# lm709_discrete.net
KiCad netlist of a schematic drawn in EAGLE
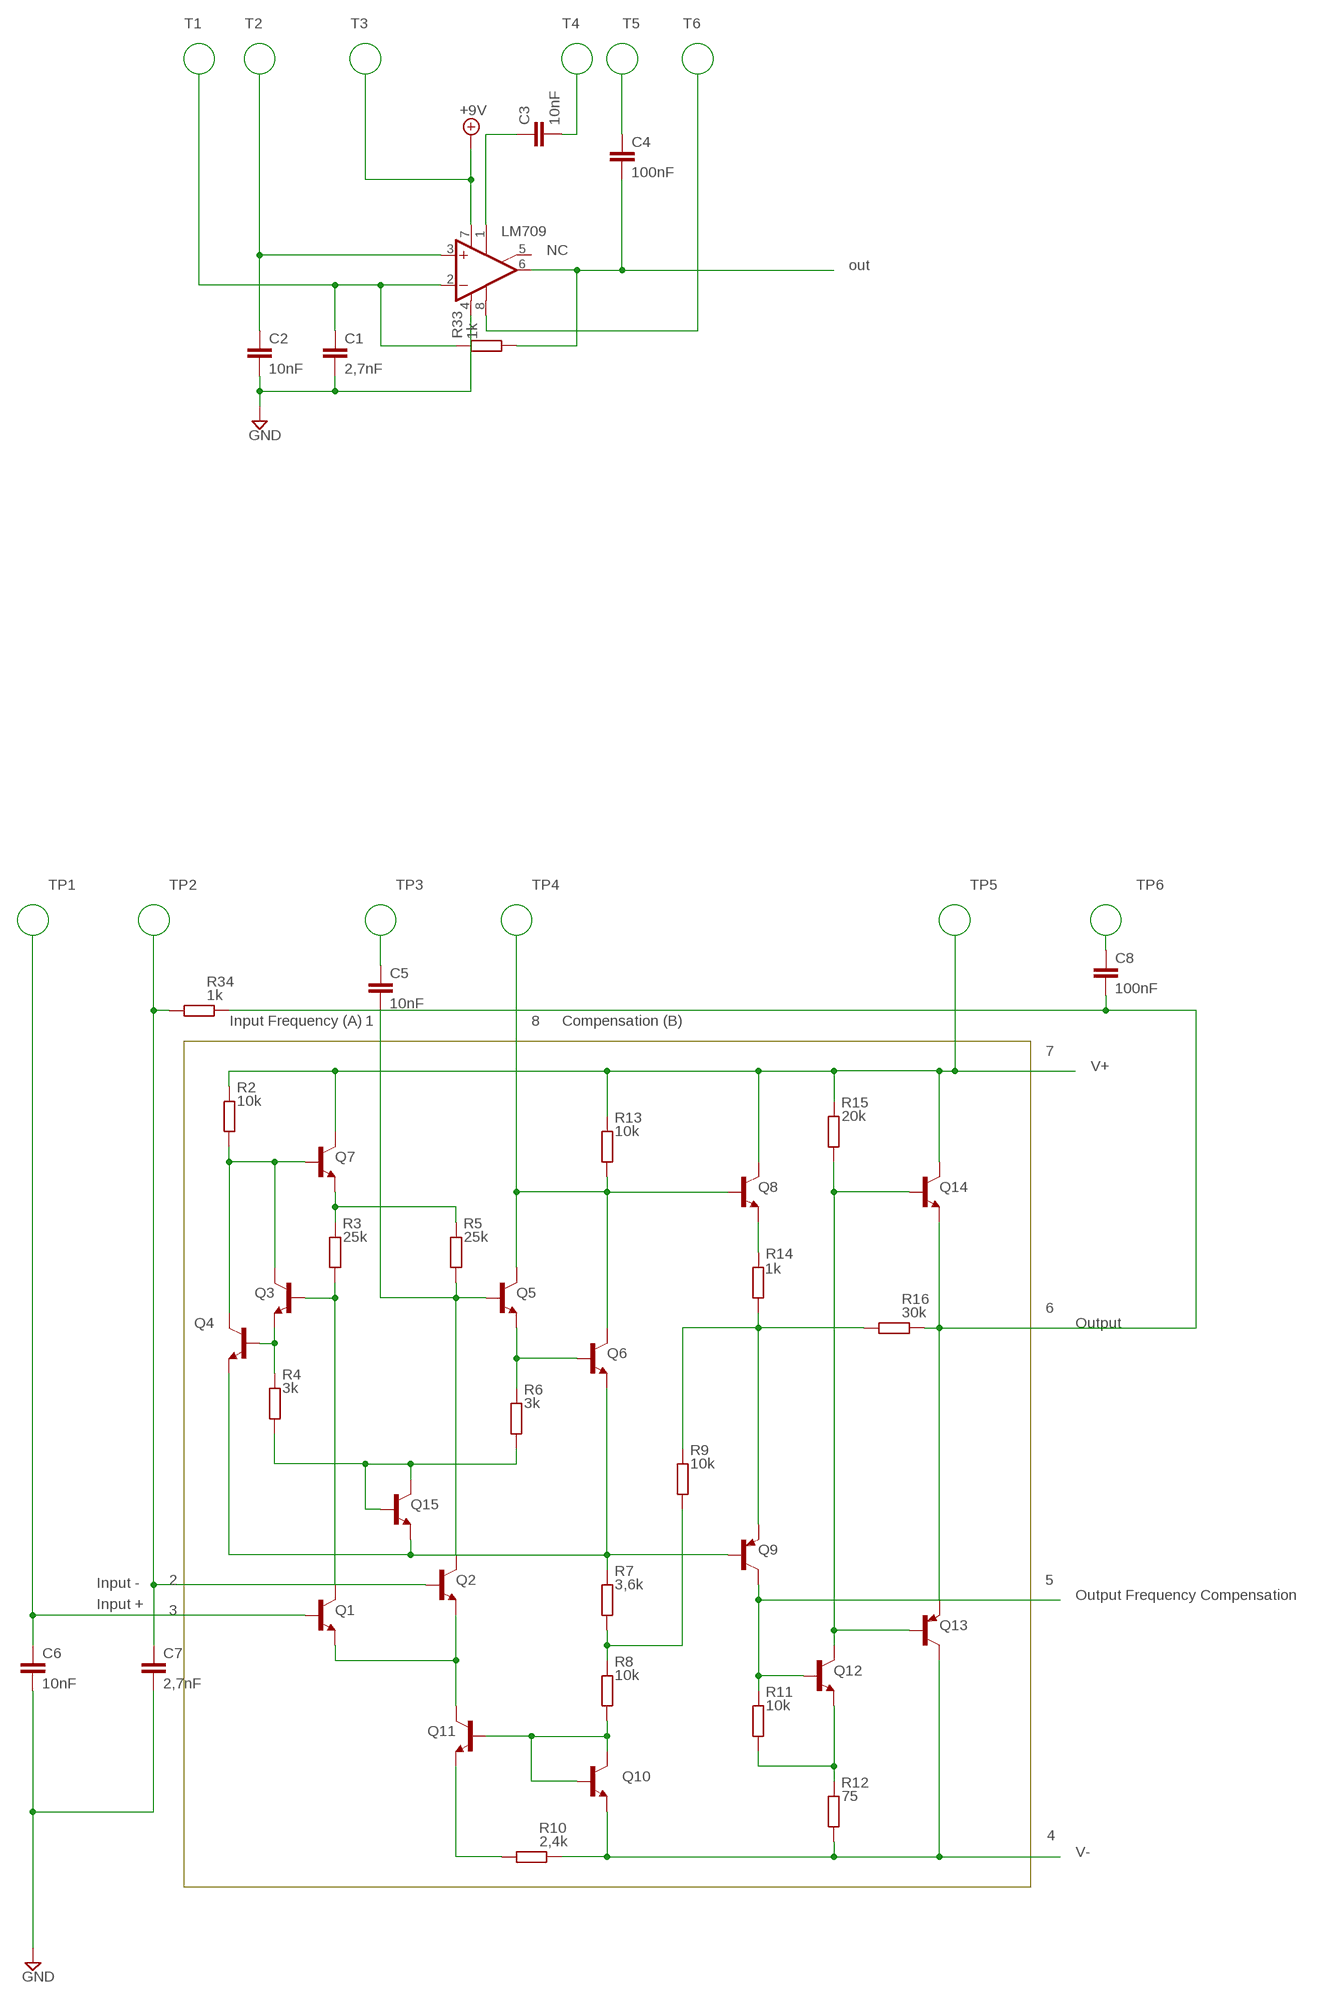
[diagram p0: schematic, sheet 1]
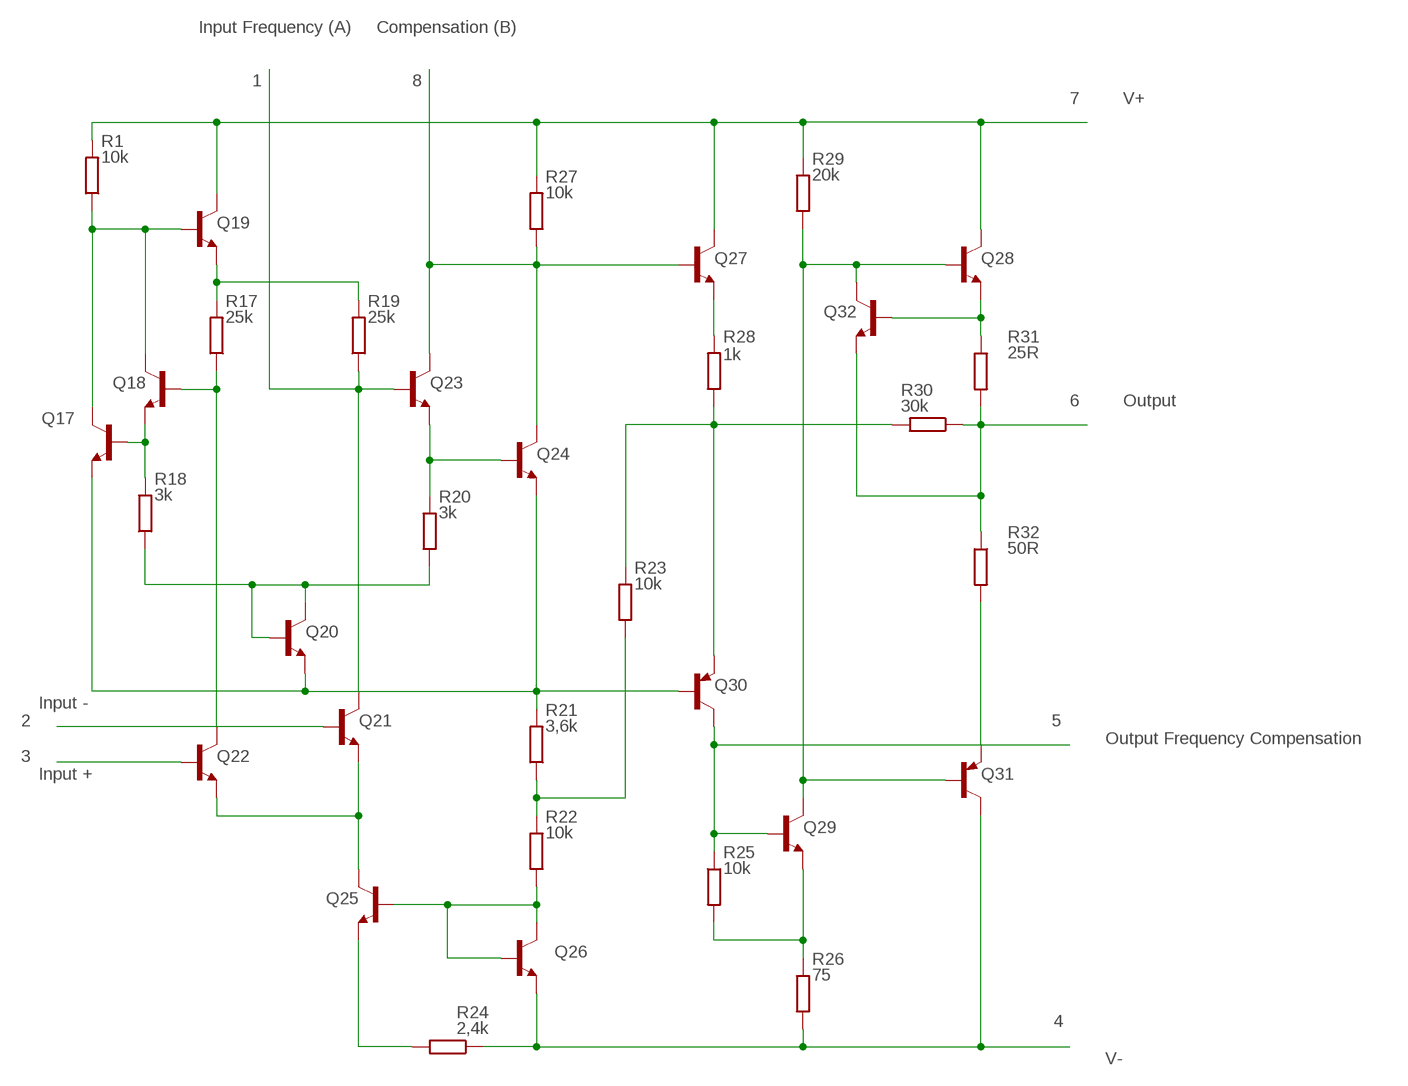
[diagram p1: schematic, sheet 2]

(export (version "E")
  (design (tool "Eeschema 10.0.6"))
  (components
    (comp (ref "C1")
      (value "2,7nF")
      (footprint "eagle-import:C025-024X044")
      (libsource (lib "eagle-import") (part "C-EU025-024X044"))
    )
    (comp (ref "C2")
      (value "10nF")
      (footprint "eagle-import:C025-024X044")
      (libsource (lib "eagle-import") (part "C-EU025-024X044"))
    )
    (comp (ref "C3")
      (value "10nF")
      (footprint "eagle-import:C025-024X044")
      (libsource (lib "eagle-import") (part "C-EU025-024X044"))
    )
    (comp (ref "C4")
      (value "100nF")
      (footprint "eagle-import:C025-024X044")
      (libsource (lib "eagle-import") (part "C-EU025-024X044"))
    )
    (comp (ref "C5")
      (value "10nF")
      (footprint "eagle-import:C025-024X044")
      (libsource (lib "eagle-import") (part "C-EU025-024X044"))
    )
    (comp (ref "C6")
      (value "10nF")
      (footprint "eagle-import:C025-024X044")
      (libsource (lib "eagle-import") (part "C-EU025-024X044"))
    )
    (comp (ref "C7")
      (value "2,7nF")
      (footprint "eagle-import:C025-024X044")
      (libsource (lib "eagle-import") (part "C-EU025-024X044"))
    )
    (comp (ref "C8")
      (value "100nF")
      (footprint "eagle-import:C025-024X044")
      (libsource (lib "eagle-import") (part "C-EU025-024X044"))
    )
    (comp (ref "LM709")
      (value "LM741P")
      (footprint "eagle-import:DIL08")
      (libsource (lib "eagle-import") (part "741PLM"))
    )
    (comp (ref "Q1")
      (value "2N3904")
      (footprint "eagle-import:TO92")
      (libsource (lib "eagle-import") (part "2N3904"))
    )
    (comp (ref "Q2")
      (value "2N3904")
      (footprint "eagle-import:TO92")
      (libsource (lib "eagle-import") (part "2N3904"))
    )
    (comp (ref "Q3")
      (value "2N3904")
      (footprint "eagle-import:TO92")
      (libsource (lib "eagle-import") (part "2N3904"))
    )
    (comp (ref "Q4")
      (value "2N3904")
      (footprint "eagle-import:TO92")
      (libsource (lib "eagle-import") (part "2N3904"))
    )
    (comp (ref "Q5")
      (value "2N3904")
      (footprint "eagle-import:TO92")
      (libsource (lib "eagle-import") (part "2N3904"))
    )
    (comp (ref "Q6")
      (value "2N3904")
      (footprint "eagle-import:TO92")
      (libsource (lib "eagle-import") (part "2N3904"))
    )
    (comp (ref "Q7")
      (value "2N3904")
      (footprint "eagle-import:TO92")
      (libsource (lib "eagle-import") (part "2N3904"))
    )
    (comp (ref "Q8")
      (value "2N3904")
      (footprint "eagle-import:TO92")
      (libsource (lib "eagle-import") (part "2N3904"))
    )
    (comp (ref "Q9")
      (value "2N3906")
      (footprint "eagle-import:TO92")
      (libsource (lib "eagle-import") (part "2N3906"))
    )
    (comp (ref "Q10")
      (value "2N3904")
      (footprint "eagle-import:TO92")
      (libsource (lib "eagle-import") (part "2N3904"))
    )
    (comp (ref "Q11")
      (value "2N3904")
      (footprint "eagle-import:TO92")
      (libsource (lib "eagle-import") (part "2N3904"))
    )
    (comp (ref "Q12")
      (value "2N3904")
      (footprint "eagle-import:TO92")
      (libsource (lib "eagle-import") (part "2N3904"))
    )
    (comp (ref "Q13")
      (value "2N3906")
      (footprint "eagle-import:TO92")
      (libsource (lib "eagle-import") (part "2N3906"))
    )
    (comp (ref "Q14")
      (value "2N3904")
      (footprint "eagle-import:TO92")
      (libsource (lib "eagle-import") (part "2N3904"))
    )
    (comp (ref "Q15")
      (value "2N3904")
      (footprint "eagle-import:TO92")
      (libsource (lib "eagle-import") (part "2N3904"))
    )
    (comp (ref "R2")
      (value "10k")
      (footprint "eagle-import:0207_10")
      (libsource (lib "eagle-import") (part "R-EU_0207/10"))
    )
    (comp (ref "R3")
      (value "25k")
      (footprint "eagle-import:0207_10")
      (libsource (lib "eagle-import") (part "R-EU_0207/10"))
    )
    (comp (ref "R4")
      (value "3k")
      (footprint "eagle-import:0207_10")
      (libsource (lib "eagle-import") (part "R-EU_0207/10"))
    )
    (comp (ref "R5")
      (value "25k")
      (footprint "eagle-import:0207_10")
      (libsource (lib "eagle-import") (part "R-EU_0207/10"))
    )
    (comp (ref "R6")
      (value "3k")
      (footprint "eagle-import:0207_10")
      (libsource (lib "eagle-import") (part "R-EU_0207/10"))
    )
    (comp (ref "R7")
      (value "3,6k")
      (footprint "eagle-import:0207_10")
      (libsource (lib "eagle-import") (part "R-EU_0207/10"))
    )
    (comp (ref "R8")
      (value "10k")
      (footprint "eagle-import:0207_10")
      (libsource (lib "eagle-import") (part "R-EU_0207/10"))
    )
    (comp (ref "R9")
      (value "10k")
      (footprint "eagle-import:0207_10")
      (libsource (lib "eagle-import") (part "R-EU_0207/10"))
    )
    (comp (ref "R10")
      (value "2,4k")
      (footprint "eagle-import:0207_10")
      (libsource (lib "eagle-import") (part "R-EU_0207/10"))
    )
    (comp (ref "R11")
      (value "10k")
      (footprint "eagle-import:0207_10")
      (libsource (lib "eagle-import") (part "R-EU_0207/10"))
    )
    (comp (ref "R12")
      (value "75")
      (footprint "eagle-import:0207_10")
      (libsource (lib "eagle-import") (part "R-EU_0207/10"))
    )
    (comp (ref "R13")
      (value "10k")
      (footprint "eagle-import:0207_10")
      (libsource (lib "eagle-import") (part "R-EU_0207/10"))
    )
    (comp (ref "R14")
      (value "1k")
      (footprint "eagle-import:0207_10")
      (libsource (lib "eagle-import") (part "R-EU_0207/10"))
    )
    (comp (ref "R15")
      (value "20k")
      (footprint "eagle-import:0207_10")
      (libsource (lib "eagle-import") (part "R-EU_0207/10"))
    )
    (comp (ref "R16")
      (value "30k")
      (footprint "eagle-import:0207_10")
      (libsource (lib "eagle-import") (part "R-EU_0207/10"))
    )
    (comp (ref "R33")
      (value "1k")
      (footprint "eagle-import:0207_10")
      (libsource (lib "eagle-import") (part "R-EU_0207/10"))
    )
    (comp (ref "R34")
      (value "1k")
      (footprint "eagle-import:0207_10")
      (libsource (lib "eagle-import") (part "R-EU_0207/10"))
    )
    (comp (ref "Q17")
      (value "2N3904")
      (footprint "eagle-import:TO92")
      (libsource (lib "eagle-import") (part "2N3904"))
    )
    (comp (ref "Q18")
      (value "2N3904")
      (footprint "eagle-import:TO92")
      (libsource (lib "eagle-import") (part "2N3904"))
    )
    (comp (ref "Q19")
      (value "2N3904")
      (footprint "eagle-import:TO92")
      (libsource (lib "eagle-import") (part "2N3904"))
    )
    (comp (ref "Q20")
      (value "2N3904")
      (footprint "eagle-import:TO92")
      (libsource (lib "eagle-import") (part "2N3904"))
    )
    (comp (ref "Q21")
      (value "2N3904")
      (footprint "eagle-import:TO92")
      (libsource (lib "eagle-import") (part "2N3904"))
    )
    (comp (ref "Q22")
      (value "2N3904")
      (footprint "eagle-import:TO92")
      (libsource (lib "eagle-import") (part "2N3904"))
    )
    (comp (ref "Q23")
      (value "2N3904")
      (footprint "eagle-import:TO92")
      (libsource (lib "eagle-import") (part "2N3904"))
    )
    (comp (ref "Q24")
      (value "2N3904")
      (footprint "eagle-import:TO92")
      (libsource (lib "eagle-import") (part "2N3904"))
    )
    (comp (ref "Q25")
      (value "2N3904")
      (footprint "eagle-import:TO92")
      (libsource (lib "eagle-import") (part "2N3904"))
    )
    (comp (ref "Q26")
      (value "2N3904")
      (footprint "eagle-import:TO92")
      (libsource (lib "eagle-import") (part "2N3904"))
    )
    (comp (ref "Q27")
      (value "2N3904")
      (footprint "eagle-import:TO92")
      (libsource (lib "eagle-import") (part "2N3904"))
    )
    (comp (ref "Q28")
      (value "2N3904")
      (footprint "eagle-import:TO92")
      (libsource (lib "eagle-import") (part "2N3904"))
    )
    (comp (ref "Q29")
      (value "2N3904")
      (footprint "eagle-import:TO92")
      (libsource (lib "eagle-import") (part "2N3904"))
    )
    (comp (ref "Q30")
      (value "2N3906")
      (footprint "eagle-import:TO92")
      (libsource (lib "eagle-import") (part "2N3906"))
    )
    (comp (ref "Q31")
      (value "2N3906")
      (footprint "eagle-import:TO92")
      (libsource (lib "eagle-import") (part "2N3906"))
    )
    (comp (ref "Q32")
      (value "2N3904")
      (footprint "eagle-import:TO92")
      (libsource (lib "eagle-import") (part "2N3904"))
    )
    (comp (ref "R1")
      (value "10k")
      (footprint "eagle-import:0207_10")
      (libsource (lib "eagle-import") (part "R-EU_0207/10"))
    )
    (comp (ref "R17")
      (value "25k")
      (footprint "eagle-import:0207_10")
      (libsource (lib "eagle-import") (part "R-EU_0207/10"))
    )
    (comp (ref "R18")
      (value "3k")
      (footprint "eagle-import:0207_10")
      (libsource (lib "eagle-import") (part "R-EU_0207/10"))
    )
    (comp (ref "R19")
      (value "25k")
      (footprint "eagle-import:0207_10")
      (libsource (lib "eagle-import") (part "R-EU_0207/10"))
    )
    (comp (ref "R20")
      (value "3k")
      (footprint "eagle-import:0207_10")
      (libsource (lib "eagle-import") (part "R-EU_0207/10"))
    )
    (comp (ref "R21")
      (value "3,6k")
      (footprint "eagle-import:0207_10")
      (libsource (lib "eagle-import") (part "R-EU_0207/10"))
    )
    (comp (ref "R22")
      (value "10k")
      (footprint "eagle-import:0207_10")
      (libsource (lib "eagle-import") (part "R-EU_0207/10"))
    )
    (comp (ref "R23")
      (value "10k")
      (footprint "eagle-import:0207_10")
      (libsource (lib "eagle-import") (part "R-EU_0207/10"))
    )
    (comp (ref "R24")
      (value "2,4k")
      (footprint "eagle-import:0207_10")
      (libsource (lib "eagle-import") (part "R-EU_0207/10"))
    )
    (comp (ref "R25")
      (value "10k")
      (footprint "eagle-import:0207_10")
      (libsource (lib "eagle-import") (part "R-EU_0207/10"))
    )
    (comp (ref "R26")
      (value "75")
      (footprint "eagle-import:0207_10")
      (libsource (lib "eagle-import") (part "R-EU_0207/10"))
    )
    (comp (ref "R27")
      (value "10k")
      (footprint "eagle-import:0207_10")
      (libsource (lib "eagle-import") (part "R-EU_0207/10"))
    )
    (comp (ref "R28")
      (value "1k")
      (footprint "eagle-import:0207_10")
      (libsource (lib "eagle-import") (part "R-EU_0207/10"))
    )
    (comp (ref "R29")
      (value "20k")
      (footprint "eagle-import:0207_10")
      (libsource (lib "eagle-import") (part "R-EU_0207/10"))
    )
    (comp (ref "R30")
      (value "30k")
      (footprint "eagle-import:0207_10")
      (libsource (lib "eagle-import") (part "R-EU_0207/10"))
    )
    (comp (ref "R31")
      (value "25R")
      (footprint "eagle-import:0207_10")
      (libsource (lib "eagle-import") (part "R-EU_0207/10"))
    )
    (comp (ref "R32")
      (value "50R")
      (footprint "eagle-import:0207_10")
      (libsource (lib "eagle-import") (part "R-EU_0207/10"))
    )
  )
  (nets
    (net (code "1") (name "+9V") (class "Default")
      (node (ref "LM709") (pin "7") (pinfunction "V+_7") (pintype "power_in"))
    )
    (net (code "2") (name "GND") (class "Default")
      (node (ref "C1") (pin "2") (pinfunction "2_2") (pintype "passive"))
      (node (ref "C2") (pin "2") (pinfunction "2_2") (pintype "passive"))
      (node (ref "C6") (pin "2") (pinfunction "2_2") (pintype "passive"))
      (node (ref "C7") (pin "2") (pinfunction "2_2") (pintype "passive"))
      (node (ref "LM709") (pin "4") (pinfunction "V-_4") (pintype "power_in"))
    )
    (net (code "3") (name "Net-(LM709-+IN)") (class "Default")
      (node (ref "C2") (pin "1") (pinfunction "1_1") (pintype "passive"))
      (node (ref "LM709") (pin "3") (pinfunction "+IN_3") (pintype "input"))
    )
    (net (code "4") (name "Net-(LM709--IN)") (class "Default")
      (node (ref "C1") (pin "1") (pinfunction "1_1") (pintype "passive"))
      (node (ref "LM709") (pin "2") (pinfunction "-IN_2") (pintype "input"))
      (node (ref "R33") (pin "2") (pinfunction "2_2") (pintype "passive"))
    )
    (net (code "5") (name "Net-(LM709-ON1)") (class "Default")
      (node (ref "C3") (pin "1") (pinfunction "1_1") (pintype "passive"))
      (node (ref "LM709") (pin "1") (pinfunction "ON1_1") (pintype "passive"))
    )
    (net (code "6") (name "Net-(LM709-OUT)") (class "Default")
      (node (ref "C4") (pin "2") (pinfunction "2_2") (pintype "passive"))
      (node (ref "LM709") (pin "6") (pinfunction "OUT_6") (pintype "output"))
      (node (ref "R33") (pin "1") (pinfunction "1_1") (pintype "passive"))
    )
    (net (code "7") (name "Net-(Q1-B)") (class "Default")
      (node (ref "C6") (pin "1") (pinfunction "1_1") (pintype "passive"))
      (node (ref "Q1") (pin "2") (pinfunction "B_2") (pintype "passive"))
    )
    (net (code "8") (name "Net-(Q1-C)") (class "Default")
      (node (ref "Q1") (pin "1") (pinfunction "C_1") (pintype "passive"))
      (node (ref "Q3") (pin "2") (pinfunction "B_2") (pintype "passive"))
      (node (ref "R3") (pin "1") (pinfunction "1_1") (pintype "passive"))
    )
    (net (code "9") (name "Net-(Q1-E)") (class "Default")
      (node (ref "Q1") (pin "3") (pinfunction "E_3") (pintype "passive"))
      (node (ref "Q11") (pin "1") (pinfunction "C_1") (pintype "passive"))
      (node (ref "Q2") (pin "3") (pinfunction "E_3") (pintype "passive"))
    )
    (net (code "10") (name "Net-(Q2-B)") (class "Default")
      (node (ref "C7") (pin "1") (pinfunction "1_1") (pintype "passive"))
      (node (ref "Q2") (pin "2") (pinfunction "B_2") (pintype "passive"))
      (node (ref "R34") (pin "2") (pinfunction "2_2") (pintype "passive"))
    )
    (net (code "11") (name "Net-(Q2-C)") (class "Default")
      (node (ref "C5") (pin "2") (pinfunction "2_2") (pintype "passive"))
      (node (ref "Q2") (pin "1") (pinfunction "C_1") (pintype "passive"))
      (node (ref "Q5") (pin "2") (pinfunction "B_2") (pintype "passive"))
      (node (ref "R5") (pin "1") (pinfunction "1_1") (pintype "passive"))
    )
    (net (code "12") (name "Net-(Q3-C)") (class "Default")
      (node (ref "Q3") (pin "1") (pinfunction "C_1") (pintype "passive"))
      (node (ref "Q4") (pin "1") (pinfunction "C_1") (pintype "passive"))
      (node (ref "Q7") (pin "2") (pinfunction "B_2") (pintype "passive"))
      (node (ref "R2") (pin "1") (pinfunction "1_1") (pintype "passive"))
    )
    (net (code "13") (name "Net-(Q3-E)") (class "Default")
      (node (ref "Q3") (pin "3") (pinfunction "E_3") (pintype "passive"))
      (node (ref "Q4") (pin "2") (pinfunction "B_2") (pintype "passive"))
      (node (ref "R4") (pin "2") (pinfunction "2_2") (pintype "passive"))
    )
    (net (code "14") (name "Net-(Q5-C)") (class "Default")
      (node (ref "Q5") (pin "1") (pinfunction "C_1") (pintype "passive"))
      (node (ref "Q6") (pin "1") (pinfunction "C_1") (pintype "passive"))
      (node (ref "Q8") (pin "2") (pinfunction "B_2") (pintype "passive"))
      (node (ref "R13") (pin "1") (pinfunction "1_1") (pintype "passive"))
    )
    (net (code "15") (name "Net-(Q5-E)") (class "Default")
      (node (ref "Q5") (pin "3") (pinfunction "E_3") (pintype "passive"))
      (node (ref "Q6") (pin "2") (pinfunction "B_2") (pintype "passive"))
      (node (ref "R6") (pin "2") (pinfunction "2_2") (pintype "passive"))
    )
    (net (code "16") (name "Net-(Q7-E)") (class "Default")
      (node (ref "Q7") (pin "3") (pinfunction "E_3") (pintype "passive"))
      (node (ref "R3") (pin "2") (pinfunction "2_2") (pintype "passive"))
      (node (ref "R5") (pin "2") (pinfunction "2_2") (pintype "passive"))
    )
    (net (code "17") (name "Net-(Q8-E)") (class "Default")
      (node (ref "Q8") (pin "3") (pinfunction "E_3") (pintype "passive"))
      (node (ref "R14") (pin "2") (pinfunction "2_2") (pintype "passive"))
    )
    (net (code "18") (name "Net-(Q9-E)") (class "Default")
      (node (ref "Q9") (pin "3") (pinfunction "E_3") (pintype "passive"))
      (node (ref "R14") (pin "1") (pinfunction "1_1") (pintype "passive"))
      (node (ref "R16") (pin "2") (pinfunction "2_2") (pintype "passive"))
      (node (ref "R9") (pin "2") (pinfunction "2_2") (pintype "passive"))
    )
    (net (code "19") (name "Net-(Q10-B)") (class "Default")
      (node (ref "Q10") (pin "1") (pinfunction "C_1") (pintype "passive"))
      (node (ref "Q10") (pin "2") (pinfunction "B_2") (pintype "passive"))
      (node (ref "Q11") (pin "2") (pinfunction "B_2") (pintype "passive"))
      (node (ref "R8") (pin "1") (pinfunction "1_1") (pintype "passive"))
    )
    (net (code "20") (name "Net-(Q10-E)") (class "Default")
      (node (ref "Q10") (pin "3") (pinfunction "E_3") (pintype "passive"))
      (node (ref "Q13") (pin "1") (pinfunction "C_1") (pintype "passive"))
      (node (ref "R10") (pin "1") (pinfunction "1_1") (pintype "passive"))
      (node (ref "R12") (pin "2") (pinfunction "2_2") (pintype "passive"))
    )
    (net (code "21") (name "Net-(Q11-E)") (class "Default")
      (node (ref "Q11") (pin "3") (pinfunction "E_3") (pintype "passive"))
      (node (ref "R10") (pin "2") (pinfunction "2_2") (pintype "passive"))
    )
    (net (code "22") (name "Net-(Q12-B)") (class "Default")
      (node (ref "Q12") (pin "2") (pinfunction "B_2") (pintype "passive"))
      (node (ref "Q9") (pin "1") (pinfunction "C_1") (pintype "passive"))
      (node (ref "R11") (pin "1") (pinfunction "1_1") (pintype "passive"))
    )
    (net (code "23") (name "Net-(Q12-C)") (class "Default")
      (node (ref "Q12") (pin "1") (pinfunction "C_1") (pintype "passive"))
      (node (ref "Q13") (pin "2") (pinfunction "B_2") (pintype "passive"))
      (node (ref "Q14") (pin "2") (pinfunction "B_2") (pintype "passive"))
      (node (ref "R15") (pin "1") (pinfunction "1_1") (pintype "passive"))
    )
    (net (code "24") (name "Net-(Q12-E)") (class "Default")
      (node (ref "Q12") (pin "3") (pinfunction "E_3") (pintype "passive"))
      (node (ref "R11") (pin "2") (pinfunction "2_2") (pintype "passive"))
      (node (ref "R12") (pin "1") (pinfunction "1_1") (pintype "passive"))
    )
    (net (code "25") (name "Net-(Q13-E)") (class "Default")
      (node (ref "C8") (pin "2") (pinfunction "2_2") (pintype "passive"))
      (node (ref "Q13") (pin "3") (pinfunction "E_3") (pintype "passive"))
      (node (ref "Q14") (pin "3") (pinfunction "E_3") (pintype "passive"))
      (node (ref "R16") (pin "1") (pinfunction "1_1") (pintype "passive"))
      (node (ref "R34") (pin "1") (pinfunction "1_1") (pintype "passive"))
    )
    (net (code "26") (name "Net-(Q14-C)") (class "Default")
      (node (ref "Q14") (pin "1") (pinfunction "C_1") (pintype "passive"))
      (node (ref "Q7") (pin "1") (pinfunction "C_1") (pintype "passive"))
      (node (ref "Q8") (pin "1") (pinfunction "C_1") (pintype "passive"))
      (node (ref "R13") (pin "2") (pinfunction "2_2") (pintype "passive"))
      (node (ref "R15") (pin "2") (pinfunction "2_2") (pintype "passive"))
      (node (ref "R2") (pin "2") (pinfunction "2_2") (pintype "passive"))
    )
    (net (code "27") (name "Net-(Q15-B)") (class "Default")
      (node (ref "Q15") (pin "1") (pinfunction "C_1") (pintype "passive"))
      (node (ref "Q15") (pin "2") (pinfunction "B_2") (pintype "passive"))
      (node (ref "R4") (pin "1") (pinfunction "1_1") (pintype "passive"))
      (node (ref "R6") (pin "1") (pinfunction "1_1") (pintype "passive"))
    )
    (net (code "28") (name "Net-(Q15-E)") (class "Default")
      (node (ref "Q15") (pin "3") (pinfunction "E_3") (pintype "passive"))
      (node (ref "Q4") (pin "3") (pinfunction "E_3") (pintype "passive"))
      (node (ref "Q6") (pin "3") (pinfunction "E_3") (pintype "passive"))
      (node (ref "Q9") (pin "2") (pinfunction "B_2") (pintype "passive"))
      (node (ref "R7") (pin "2") (pinfunction "2_2") (pintype "passive"))
    )
    (net (code "29") (name "Net-(Q17-B)") (class "Default")
      (node (ref "Q17") (pin "2") (pinfunction "B_2") (pintype "passive"))
      (node (ref "Q18") (pin "3") (pinfunction "E_3") (pintype "passive"))
      (node (ref "R18") (pin "2") (pinfunction "2_2") (pintype "passive"))
    )
    (net (code "30") (name "Net-(Q17-C)") (class "Default")
      (node (ref "Q17") (pin "1") (pinfunction "C_1") (pintype "passive"))
      (node (ref "Q18") (pin "1") (pinfunction "C_1") (pintype "passive"))
      (node (ref "Q19") (pin "2") (pinfunction "B_2") (pintype "passive"))
      (node (ref "R1") (pin "1") (pinfunction "1_1") (pintype "passive"))
    )
    (net (code "31") (name "Net-(Q17-E)") (class "Default")
      (node (ref "Q17") (pin "3") (pinfunction "E_3") (pintype "passive"))
      (node (ref "Q20") (pin "3") (pinfunction "E_3") (pintype "passive"))
      (node (ref "Q24") (pin "3") (pinfunction "E_3") (pintype "passive"))
      (node (ref "Q30") (pin "2") (pinfunction "B_2") (pintype "passive"))
      (node (ref "R21") (pin "2") (pinfunction "2_2") (pintype "passive"))
    )
    (net (code "32") (name "Net-(Q18-B)") (class "Default")
      (node (ref "Q18") (pin "2") (pinfunction "B_2") (pintype "passive"))
      (node (ref "Q22") (pin "1") (pinfunction "C_1") (pintype "passive"))
      (node (ref "R17") (pin "1") (pinfunction "1_1") (pintype "passive"))
    )
    (net (code "33") (name "Net-(Q19-C)") (class "Default")
      (node (ref "Q19") (pin "1") (pinfunction "C_1") (pintype "passive"))
      (node (ref "Q27") (pin "1") (pinfunction "C_1") (pintype "passive"))
      (node (ref "Q28") (pin "1") (pinfunction "C_1") (pintype "passive"))
      (node (ref "R1") (pin "2") (pinfunction "2_2") (pintype "passive"))
      (node (ref "R27") (pin "2") (pinfunction "2_2") (pintype "passive"))
      (node (ref "R29") (pin "2") (pinfunction "2_2") (pintype "passive"))
    )
    (net (code "34") (name "Net-(Q19-E)") (class "Default")
      (node (ref "Q19") (pin "3") (pinfunction "E_3") (pintype "passive"))
      (node (ref "R17") (pin "2") (pinfunction "2_2") (pintype "passive"))
      (node (ref "R19") (pin "2") (pinfunction "2_2") (pintype "passive"))
    )
    (net (code "35") (name "Net-(Q20-B)") (class "Default")
      (node (ref "Q20") (pin "1") (pinfunction "C_1") (pintype "passive"))
      (node (ref "Q20") (pin "2") (pinfunction "B_2") (pintype "passive"))
      (node (ref "R18") (pin "1") (pinfunction "1_1") (pintype "passive"))
      (node (ref "R20") (pin "1") (pinfunction "1_1") (pintype "passive"))
    )
    (net (code "36") (name "Net-(Q21-C)") (class "Default")
      (node (ref "Q21") (pin "1") (pinfunction "C_1") (pintype "passive"))
      (node (ref "Q23") (pin "2") (pinfunction "B_2") (pintype "passive"))
      (node (ref "R19") (pin "1") (pinfunction "1_1") (pintype "passive"))
    )
    (net (code "37") (name "Net-(Q21-E)") (class "Default")
      (node (ref "Q21") (pin "3") (pinfunction "E_3") (pintype "passive"))
      (node (ref "Q22") (pin "3") (pinfunction "E_3") (pintype "passive"))
      (node (ref "Q25") (pin "1") (pinfunction "C_1") (pintype "passive"))
    )
    (net (code "38") (name "Net-(Q23-C)") (class "Default")
      (node (ref "Q23") (pin "1") (pinfunction "C_1") (pintype "passive"))
      (node (ref "Q24") (pin "1") (pinfunction "C_1") (pintype "passive"))
      (node (ref "Q27") (pin "2") (pinfunction "B_2") (pintype "passive"))
      (node (ref "R27") (pin "1") (pinfunction "1_1") (pintype "passive"))
    )
    (net (code "39") (name "Net-(Q23-E)") (class "Default")
      (node (ref "Q23") (pin "3") (pinfunction "E_3") (pintype "passive"))
      (node (ref "Q24") (pin "2") (pinfunction "B_2") (pintype "passive"))
      (node (ref "R20") (pin "2") (pinfunction "2_2") (pintype "passive"))
    )
    (net (code "40") (name "Net-(Q25-B)") (class "Default")
      (node (ref "Q25") (pin "2") (pinfunction "B_2") (pintype "passive"))
      (node (ref "Q26") (pin "1") (pinfunction "C_1") (pintype "passive"))
      (node (ref "Q26") (pin "2") (pinfunction "B_2") (pintype "passive"))
      (node (ref "R22") (pin "1") (pinfunction "1_1") (pintype "passive"))
    )
    (net (code "41") (name "Net-(Q25-E)") (class "Default")
      (node (ref "Q25") (pin "3") (pinfunction "E_3") (pintype "passive"))
      (node (ref "R24") (pin "2") (pinfunction "2_2") (pintype "passive"))
    )
    (net (code "42") (name "Net-(Q26-E)") (class "Default")
      (node (ref "Q26") (pin "3") (pinfunction "E_3") (pintype "passive"))
      (node (ref "Q31") (pin "1") (pinfunction "C_1") (pintype "passive"))
      (node (ref "R24") (pin "1") (pinfunction "1_1") (pintype "passive"))
      (node (ref "R26") (pin "2") (pinfunction "2_2") (pintype "passive"))
    )
    (net (code "43") (name "Net-(Q27-E)") (class "Default")
      (node (ref "Q27") (pin "3") (pinfunction "E_3") (pintype "passive"))
      (node (ref "R28") (pin "2") (pinfunction "2_2") (pintype "passive"))
    )
    (net (code "44") (name "Net-(Q28-B)") (class "Default")
      (node (ref "Q28") (pin "2") (pinfunction "B_2") (pintype "passive"))
      (node (ref "Q29") (pin "1") (pinfunction "C_1") (pintype "passive"))
      (node (ref "Q31") (pin "2") (pinfunction "B_2") (pintype "passive"))
      (node (ref "Q32") (pin "1") (pinfunction "C_1") (pintype "passive"))
      (node (ref "R29") (pin "1") (pinfunction "1_1") (pintype "passive"))
    )
    (net (code "45") (name "Net-(Q28-E)") (class "Default")
      (node (ref "Q28") (pin "3") (pinfunction "E_3") (pintype "passive"))
      (node (ref "Q32") (pin "2") (pinfunction "B_2") (pintype "passive"))
      (node (ref "R31") (pin "1") (pinfunction "1_1") (pintype "passive"))
    )
    (net (code "46") (name "Net-(Q29-B)") (class "Default")
      (node (ref "Q29") (pin "2") (pinfunction "B_2") (pintype "passive"))
      (node (ref "Q30") (pin "1") (pinfunction "C_1") (pintype "passive"))
      (node (ref "R25") (pin "1") (pinfunction "1_1") (pintype "passive"))
    )
    (net (code "47") (name "Net-(Q29-E)") (class "Default")
      (node (ref "Q29") (pin "3") (pinfunction "E_3") (pintype "passive"))
      (node (ref "R25") (pin "2") (pinfunction "2_2") (pintype "passive"))
      (node (ref "R26") (pin "1") (pinfunction "1_1") (pintype "passive"))
    )
    (net (code "48") (name "Net-(Q30-E)") (class "Default")
      (node (ref "Q30") (pin "3") (pinfunction "E_3") (pintype "passive"))
      (node (ref "R23") (pin "2") (pinfunction "2_2") (pintype "passive"))
      (node (ref "R28") (pin "1") (pinfunction "1_1") (pintype "passive"))
      (node (ref "R30") (pin "2") (pinfunction "2_2") (pintype "passive"))
    )
    (net (code "49") (name "Net-(Q31-E)") (class "Default")
      (node (ref "Q31") (pin "3") (pinfunction "E_3") (pintype "passive"))
      (node (ref "R32") (pin "2") (pinfunction "2_2") (pintype "passive"))
    )
    (net (code "50") (name "Net-(Q32-E)") (class "Default")
      (node (ref "Q32") (pin "3") (pinfunction "E_3") (pintype "passive"))
      (node (ref "R30") (pin "1") (pinfunction "1_1") (pintype "passive"))
      (node (ref "R31") (pin "2") (pinfunction "2_2") (pintype "passive"))
      (node (ref "R32") (pin "1") (pinfunction "1_1") (pintype "passive"))
    )
    (net (code "51") (name "Net-(R7-Pad1)") (class "Default")
      (node (ref "R7") (pin "1") (pinfunction "1_1") (pintype "passive"))
      (node (ref "R8") (pin "2") (pinfunction "2_2") (pintype "passive"))
      (node (ref "R9") (pin "1") (pinfunction "1_1") (pintype "passive"))
    )
    (net (code "52") (name "Net-(R21-Pad1)") (class "Default")
      (node (ref "R21") (pin "1") (pinfunction "1_1") (pintype "passive"))
      (node (ref "R22") (pin "2") (pinfunction "2_2") (pintype "passive"))
      (node (ref "R23") (pin "1") (pinfunction "1_1") (pintype "passive"))
    )
    (net (code "53") (name "unconnected-(C3-Pad2)") (class "Default")
      (node (ref "C3") (pin "2") (pinfunction "2_2") (pintype "passive"))
    )
    (net (code "54") (name "unconnected-(C4-Pad1)") (class "Default")
      (node (ref "C4") (pin "1") (pinfunction "1_1") (pintype "passive"))
    )
    (net (code "55") (name "unconnected-(C5-Pad1)") (class "Default")
      (node (ref "C5") (pin "1") (pinfunction "1_1") (pintype "passive"))
    )
    (net (code "56") (name "unconnected-(C8-Pad1)") (class "Default")
      (node (ref "C8") (pin "1") (pinfunction "1_1") (pintype "passive"))
    )
    (net (code "57") (name "unconnected-(LM709-ON2-Pad5)") (class "Default")
      (node (ref "LM709") (pin "5") (pinfunction "ON2_5") (pintype "passive"))
    )
    (net (code "58") (name "unconnected-(LM709-OPT-Pad8)") (class "Default")
      (node (ref "LM709") (pin "8") (pinfunction "OPT_8") (pintype "passive"))
    )
    (net (code "59") (name "unconnected-(Q21-B-Pad2)") (class "Default")
      (node (ref "Q21") (pin "2") (pinfunction "B_2") (pintype "passive"))
    )
    (net (code "60") (name "unconnected-(Q22-B-Pad2)") (class "Default")
      (node (ref "Q22") (pin "2") (pinfunction "B_2") (pintype "passive"))
    )
  )
)
